# G007X.net
KiCad netlist of a schematic drawn in EAGLE
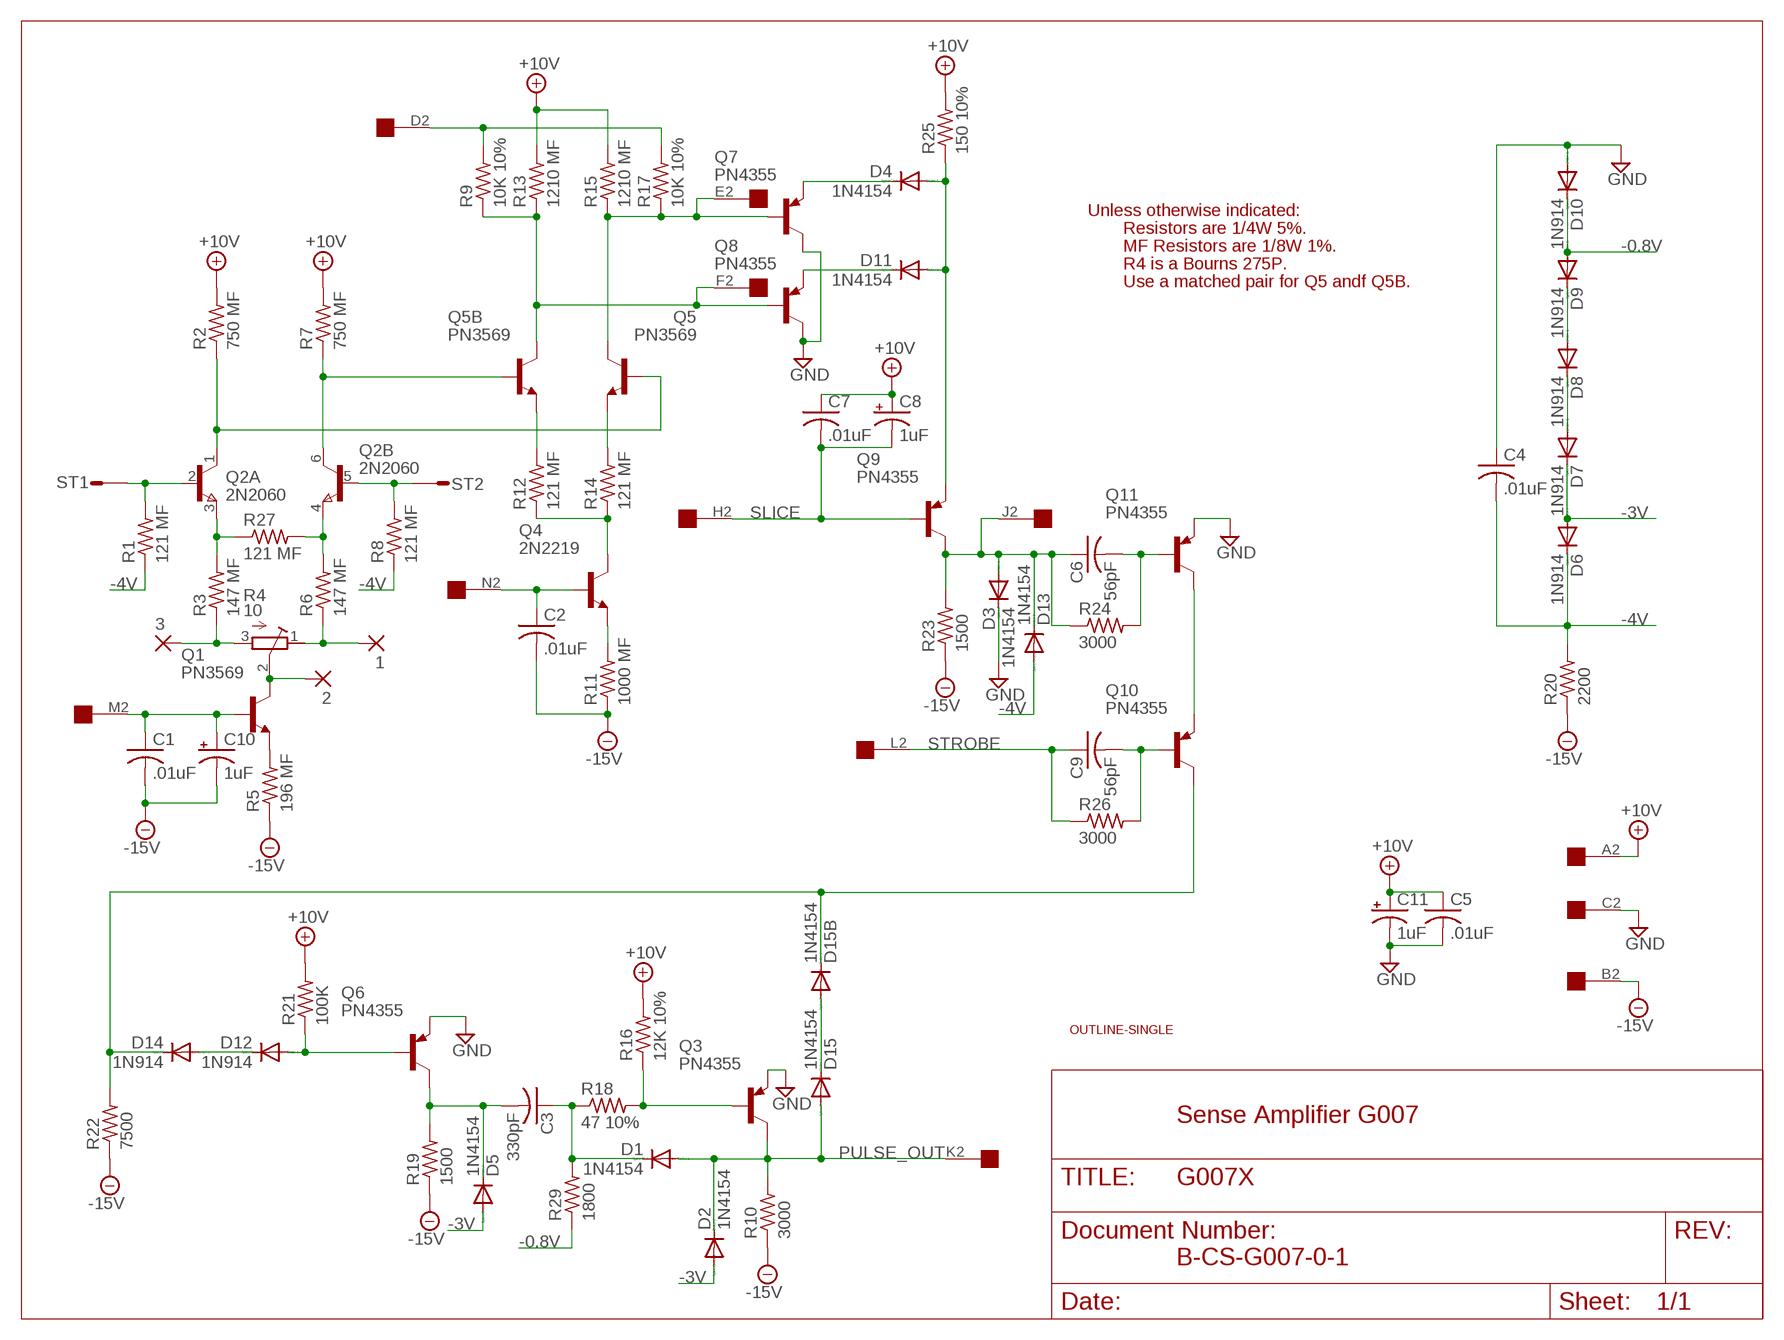
[diagram p0: schematic, sheet 1]

(export (version "E")
  (design (tool "Eeschema 10.0.6"))
  (components
    (comp (ref "1")
      (value "2,54/0,8")
      (footprint "eagle-import:2,54_0,8")
      (libsource (lib "eagle-import") (part "2,54/0,8"))
    )
    (comp (ref "2")
      (value "2,54/0,8")
      (footprint "eagle-import:2,54_0,8")
      (libsource (lib "eagle-import") (part "2,54/0,8"))
    )
    (comp (ref "3")
      (value "2,54/0,8")
      (footprint "eagle-import:2,54_0,8")
      (libsource (lib "eagle-import") (part "2,54/0,8"))
    )
    (comp (ref "C1")
      (value ".01uF")
      (footprint "eagle-import:C050-025X075")
      (libsource (lib "eagle-import") (part "C-US050-025X075"))
    )
    (comp (ref "C2")
      (value ".01uF")
      (footprint "eagle-import:C050-025X075")
      (libsource (lib "eagle-import") (part "C-US050-025X075"))
    )
    (comp (ref "C3")
      (value "330pF")
      (footprint "eagle-import:C075-032X103")
      (libsource (lib "eagle-import") (part "C-US075-032X103"))
    )
    (comp (ref "C4")
      (value ".01uF")
      (footprint "eagle-import:C050-025X075")
      (libsource (lib "eagle-import") (part "C-US050-025X075"))
    )
    (comp (ref "C5")
      (value ".01uF")
      (footprint "eagle-import:C050-025X075")
      (libsource (lib "eagle-import") (part "C-US050-025X075"))
    )
    (comp (ref "C6")
      (value "56pF")
      (footprint "eagle-import:C075-032X103")
      (libsource (lib "eagle-import") (part "C-US075-032X103"))
    )
    (comp (ref "C7")
      (value ".01uF")
      (footprint "eagle-import:C050-025X075")
      (libsource (lib "eagle-import") (part "C-US050-025X075"))
    )
    (comp (ref "C8")
      (value "1uF")
      (footprint "eagle-import:E12-4")
      (libsource (lib "eagle-import") (part "CPOL-USE12-4AXIAL"))
    )
    (comp (ref "C9")
      (value "56pF")
      (footprint "eagle-import:C075-032X103")
      (libsource (lib "eagle-import") (part "C-US075-032X103"))
    )
    (comp (ref "C10")
      (value "1uF")
      (footprint "eagle-import:E12-4")
      (libsource (lib "eagle-import") (part "CPOL-USE12-4AXIAL"))
    )
    (comp (ref "C11")
      (value "1uF")
      (footprint "eagle-import:E12-4")
      (libsource (lib "eagle-import") (part "CPOL-USE12-4AXIAL"))
    )
    (comp (ref "D1")
      (value "1N4154")
      (footprint "eagle-import:DO35-10")
      (libsource (lib "eagle-import") (part "1N4148DO35-10"))
    )
    (comp (ref "D2")
      (value "1N4154")
      (footprint "eagle-import:DO35-10")
      (libsource (lib "eagle-import") (part "1N4148DO35-10"))
    )
    (comp (ref "D3")
      (value "1N4154")
      (footprint "eagle-import:DO35-10")
      (libsource (lib "eagle-import") (part "1N4148DO35-10"))
    )
    (comp (ref "D4")
      (value "1N4154")
      (footprint "eagle-import:DO35-10")
      (libsource (lib "eagle-import") (part "1N4148DO35-10"))
    )
    (comp (ref "D5")
      (value "1N4154")
      (footprint "eagle-import:DO35-10")
      (libsource (lib "eagle-import") (part "1N4148DO35-10"))
    )
    (comp (ref "D6")
      (value "1N914")
      (footprint "eagle-import:DO35-10")
      (libsource (lib "eagle-import") (part "1N4148DO35-10"))
    )
    (comp (ref "D7")
      (value "1N914")
      (footprint "eagle-import:DO35-10")
      (libsource (lib "eagle-import") (part "1N4148DO35-10"))
    )
    (comp (ref "D8")
      (value "1N914")
      (footprint "eagle-import:DO35-10")
      (libsource (lib "eagle-import") (part "1N4148DO35-10"))
    )
    (comp (ref "D9")
      (value "1N914")
      (footprint "eagle-import:DO35-10")
      (libsource (lib "eagle-import") (part "1N4148DO35-10"))
    )
    (comp (ref "D10")
      (value "1N914")
      (footprint "eagle-import:DO35-10")
      (libsource (lib "eagle-import") (part "1N4148DO35-10"))
    )
    (comp (ref "D11")
      (value "1N4154")
      (footprint "eagle-import:DO35-10")
      (libsource (lib "eagle-import") (part "1N4148DO35-10"))
    )
    (comp (ref "D12")
      (value "1N914")
      (footprint "eagle-import:DO35-10")
      (libsource (lib "eagle-import") (part "1N4148DO35-10"))
    )
    (comp (ref "D13")
      (value "1N4154")
      (footprint "eagle-import:DO35-10")
      (libsource (lib "eagle-import") (part "1N4148DO35-10"))
    )
    (comp (ref "D14")
      (value "1N914")
      (footprint "eagle-import:DO35-10")
      (libsource (lib "eagle-import") (part "1N4148DO35-10"))
    )
    (comp (ref "D15")
      (value "1N4154")
      (footprint "eagle-import:DO35-10")
      (libsource (lib "eagle-import") (part "1N4148DO35-10"))
    )
    (comp (ref "D15B")
      (value "1N4154")
      (footprint "eagle-import:DO35-10")
      (libsource (lib "eagle-import") (part "1N4148DO35-10"))
    )
    (comp (ref "Q1")
      (value "PN3569")
      (footprint "eagle-import:TO5")
      (libsource (lib "eagle-import") (part "2N2102"))
    )
    (comp (ref "Q2")
      (value "2N2060")
      (footprint "eagle-import:TO78")
      (libsource (lib "eagle-import") (part "MAT-02H"))
    )
    (comp (ref "Q3")
      (value "PN4355")
      (footprint "eagle-import:TO39")
      (libsource (lib "eagle-import") (part "2N2904"))
    )
    (comp (ref "Q4")
      (value "2N2219")
      (footprint "eagle-import:TO5")
      (libsource (lib "eagle-import") (part "2N2102"))
    )
    (comp (ref "Q5")
      (value "PN3569")
      (footprint "eagle-import:TO5")
      (libsource (lib "eagle-import") (part "2N2102"))
    )
    (comp (ref "Q5B")
      (value "PN3569")
      (footprint "eagle-import:TO5")
      (libsource (lib "eagle-import") (part "2N2102"))
    )
    (comp (ref "Q6")
      (value "PN4355")
      (footprint "eagle-import:TO39")
      (libsource (lib "eagle-import") (part "2N2904"))
    )
    (comp (ref "Q7")
      (value "PN4355")
      (footprint "eagle-import:TO39")
      (libsource (lib "eagle-import") (part "2N2904"))
    )
    (comp (ref "Q8")
      (value "PN4355")
      (footprint "eagle-import:TO39")
      (libsource (lib "eagle-import") (part "2N2904"))
    )
    (comp (ref "Q9")
      (value "PN4355")
      (footprint "eagle-import:TO39")
      (libsource (lib "eagle-import") (part "2N2904"))
    )
    (comp (ref "Q10")
      (value "PN4355")
      (footprint "eagle-import:TO39")
      (libsource (lib "eagle-import") (part "2N2904"))
    )
    (comp (ref "Q11")
      (value "PN4355")
      (footprint "eagle-import:TO39")
      (libsource (lib "eagle-import") (part "2N2904"))
    )
    (comp (ref "R1")
      (value "121 MF")
      (footprint "eagle-import:0207_12")
      (libsource (lib "eagle-import") (part "R-US_0207/12"))
    )
    (comp (ref "R2")
      (value "750 MF")
      (footprint "eagle-import:0207_12")
      (libsource (lib "eagle-import") (part "R-US_0207/12"))
    )
    (comp (ref "R3")
      (value "147 MF")
      (footprint "eagle-import:0207_12")
      (libsource (lib "eagle-import") (part "R-US_0207/12"))
    )
    (comp (ref "R4")
      (value "10")
      (footprint "eagle-import:3006Y")
      (libsource (lib "eagle-import") (part "275P"))
    )
    (comp (ref "R5")
      (value "196 MF")
      (footprint "eagle-import:0207_12")
      (libsource (lib "eagle-import") (part "R-US_0207/12"))
    )
    (comp (ref "R6")
      (value "147 MF")
      (footprint "eagle-import:0207_12")
      (libsource (lib "eagle-import") (part "R-US_0207/12"))
    )
    (comp (ref "R7")
      (value "750 MF")
      (footprint "eagle-import:0207_12")
      (libsource (lib "eagle-import") (part "R-US_0207/12"))
    )
    (comp (ref "R8")
      (value "121 MF")
      (footprint "eagle-import:0207_12")
      (libsource (lib "eagle-import") (part "R-US_0207/12"))
    )
    (comp (ref "R9")
      (value "10K 10%")
      (footprint "eagle-import:0207_10")
      (libsource (lib "eagle-import") (part "R-US_0207/10"))
    )
    (comp (ref "R10")
      (value "3000")
      (footprint "eagle-import:0207_10")
      (libsource (lib "eagle-import") (part "R-US_0207/10"))
    )
    (comp (ref "R11")
      (value "1000 MF")
      (footprint "eagle-import:0207_12")
      (libsource (lib "eagle-import") (part "R-US_0207/12"))
    )
    (comp (ref "R12")
      (value "121 MF")
      (footprint "eagle-import:0207_12")
      (libsource (lib "eagle-import") (part "R-US_0207/12"))
    )
    (comp (ref "R13")
      (value "1210 MF")
      (footprint "eagle-import:0207_12")
      (libsource (lib "eagle-import") (part "R-US_0207/12"))
    )
    (comp (ref "R14")
      (value "121 MF")
      (footprint "eagle-import:0207_12")
      (libsource (lib "eagle-import") (part "R-US_0207/12"))
    )
    (comp (ref "R15")
      (value "1210 MF")
      (footprint "eagle-import:0207_12")
      (libsource (lib "eagle-import") (part "R-US_0207/12"))
    )
    (comp (ref "R16")
      (value "12K 10%")
      (footprint "eagle-import:0207_10")
      (libsource (lib "eagle-import") (part "R-US_0207/10"))
    )
    (comp (ref "R17")
      (value "10K 10%")
      (footprint "eagle-import:0207_10")
      (libsource (lib "eagle-import") (part "R-US_0207/10"))
    )
    (comp (ref "R18")
      (value "47 10%")
      (footprint "eagle-import:0207_10")
      (libsource (lib "eagle-import") (part "R-US_0207/10"))
    )
    (comp (ref "R19")
      (value "1500")
      (footprint "eagle-import:0207_10")
      (libsource (lib "eagle-import") (part "R-US_0207/10"))
    )
    (comp (ref "R20")
      (value "2200")
      (footprint "eagle-import:0207_10")
      (libsource (lib "eagle-import") (part "R-US_0207/10"))
    )
    (comp (ref "R21")
      (value "100K")
      (footprint "eagle-import:0207_10")
      (libsource (lib "eagle-import") (part "R-US_0207/10"))
    )
    (comp (ref "R22")
      (value "7500")
      (footprint "eagle-import:0207_10")
      (libsource (lib "eagle-import") (part "R-US_0207/10"))
    )
    (comp (ref "R23")
      (value "1500")
      (footprint "eagle-import:0207_10")
      (libsource (lib "eagle-import") (part "R-US_0207/10"))
    )
    (comp (ref "R24")
      (value "3000")
      (footprint "eagle-import:0207_10")
      (libsource (lib "eagle-import") (part "R-US_0207/10"))
    )
    (comp (ref "R25")
      (value "150 10%")
      (footprint "eagle-import:0207_10")
      (libsource (lib "eagle-import") (part "R-US_0207/10"))
    )
    (comp (ref "R26")
      (value "3000")
      (footprint "eagle-import:0207_10")
      (libsource (lib "eagle-import") (part "R-US_0207/10"))
    )
    (comp (ref "R27")
      (value "121 MF")
      (footprint "eagle-import:0207_12")
      (libsource (lib "eagle-import") (part "R-US_0207/12"))
    )
    (comp (ref "R29")
      (value "1800")
      (footprint "eagle-import:0207_10")
      (libsource (lib "eagle-import") (part "R-US_0207/10"))
    )
    (comp (ref "ST1")
      (value "ST2,8")
      (footprint "eagle-import:ST2,8")
      (libsource (lib "eagle-import") (part "ST2,8"))
    )
    (comp (ref "ST2")
      (value "ST2,8")
      (footprint "eagle-import:ST2,8")
      (libsource (lib "eagle-import") (part "ST2,8"))
    )
    (comp (ref "U$1")
      (value "OUTLINE-SINGLE")
      (footprint "eagle-import:SINGLE")
      (libsource (lib "eagle-import") (part "OUTLINE-SINGLE"))
    )
    (comp (ref "U$2")
      (value "EDGE-1")
      (footprint "eagle-import:EDGE-CON1")
      (libsource (lib "eagle-import") (part "EDGE-1"))
    )
  )
  (nets
    (net (code "1") (name "+10V") (class "Default")
      (node (ref "C11") (pin "+") (pinfunction "+_+") (pintype "passive"))
      (node (ref "C5") (pin "1") (pinfunction "1_1") (pintype "passive"))
      (node (ref "C7") (pin "1") (pinfunction "1_1") (pintype "passive"))
      (node (ref "C8") (pin "+") (pinfunction "+_+") (pintype "passive"))
      (node (ref "R13") (pin "2") (pinfunction "2_2") (pintype "passive"))
      (node (ref "R15") (pin "2") (pinfunction "2_2") (pintype "passive"))
      (node (ref "R16") (pin "2") (pinfunction "2_2") (pintype "passive"))
      (node (ref "R2") (pin "2") (pinfunction "2_2") (pintype "passive"))
      (node (ref "R21") (pin "2") (pinfunction "2_2") (pintype "passive"))
      (node (ref "R25") (pin "2") (pinfunction "2_2") (pintype "passive"))
      (node (ref "R7") (pin "2") (pinfunction "2_2") (pintype "passive"))
      (node (ref "U$2") (pin "A2") (pinfunction "1_A2") (pintype "bidirectional"))
    )
    (net (code "2") (name "-15V") (class "Default")
      (node (ref "C1") (pin "2") (pinfunction "2_2") (pintype "passive"))
      (node (ref "C10") (pin "-") (pinfunction "-_-") (pintype "passive"))
      (node (ref "C2") (pin "2") (pinfunction "2_2") (pintype "passive"))
      (node (ref "R10") (pin "1") (pinfunction "1_1") (pintype "passive"))
      (node (ref "R11") (pin "1") (pinfunction "1_1") (pintype "passive"))
      (node (ref "R19") (pin "1") (pinfunction "1_1") (pintype "passive"))
      (node (ref "R20") (pin "1") (pinfunction "1_1") (pintype "passive"))
      (node (ref "R22") (pin "1") (pinfunction "1_1") (pintype "passive"))
      (node (ref "R23") (pin "1") (pinfunction "1_1") (pintype "passive"))
      (node (ref "R5") (pin "1") (pinfunction "1_1") (pintype "passive"))
      (node (ref "U$2") (pin "B2") (pinfunction "1_B2") (pintype "bidirectional"))
    )
    (net (code "3") (name "/-0.8V") (class "Default")
      (node (ref "D10") (pin "C") (pinfunction "C_C") (pintype "passive"))
      (node (ref "D9") (pin "A") (pinfunction "A_A") (pintype "passive"))
      (node (ref "R29") (pin "1") (pinfunction "1_1") (pintype "passive"))
    )
    (net (code "4") (name "/-3V") (class "Default")
      (node (ref "D2") (pin "A") (pinfunction "A_A") (pintype "passive"))
      (node (ref "D5") (pin "A") (pinfunction "A_A") (pintype "passive"))
      (node (ref "D6") (pin "A") (pinfunction "A_A") (pintype "passive"))
      (node (ref "D7") (pin "C") (pinfunction "C_C") (pintype "passive"))
    )
    (net (code "5") (name "/-4V") (class "Default")
      (node (ref "C4") (pin "2") (pinfunction "2_2") (pintype "passive"))
      (node (ref "D13") (pin "A") (pinfunction "A_A") (pintype "passive"))
      (node (ref "D6") (pin "C") (pinfunction "C_C") (pintype "passive"))
      (node (ref "R1") (pin "1") (pinfunction "1_1") (pintype "passive"))
      (node (ref "R20") (pin "2") (pinfunction "2_2") (pintype "passive"))
      (node (ref "R8") (pin "1") (pinfunction "1_1") (pintype "passive"))
    )
    (net (code "6") (name "/PULSE_OUT") (class "Default")
      (node (ref "D1") (pin "A") (pinfunction "A_A") (pintype "passive"))
      (node (ref "D15") (pin "A") (pinfunction "A_A") (pintype "passive"))
      (node (ref "D2") (pin "C") (pinfunction "C_C") (pintype "passive"))
      (node (ref "Q3") (pin "3") (pinfunction "C_3") (pintype "passive"))
      (node (ref "R10") (pin "2") (pinfunction "2_2") (pintype "passive"))
      (node (ref "U$2") (pin "K2") (pinfunction "1_K2") (pintype "bidirectional"))
    )
    (net (code "7") (name "/SLICE") (class "Default")
      (node (ref "C7") (pin "2") (pinfunction "2_2") (pintype "passive"))
      (node (ref "C8") (pin "-") (pinfunction "-_-") (pintype "passive"))
      (node (ref "Q9") (pin "2") (pinfunction "B_2") (pintype "passive"))
      (node (ref "U$2") (pin "H2") (pinfunction "1_H2") (pintype "bidirectional"))
    )
    (net (code "8") (name "/STROBE") (class "Default")
      (node (ref "C9") (pin "1") (pinfunction "1_1") (pintype "passive"))
      (node (ref "R26") (pin "1") (pinfunction "1_1") (pintype "passive"))
      (node (ref "U$2") (pin "L2") (pinfunction "1_L2") (pintype "bidirectional"))
    )
    (net (code "9") (name "GND") (class "Default")
      (node (ref "C11") (pin "-") (pinfunction "-_-") (pintype "passive"))
      (node (ref "C4") (pin "1") (pinfunction "1_1") (pintype "passive"))
      (node (ref "C5") (pin "2") (pinfunction "2_2") (pintype "passive"))
      (node (ref "D10") (pin "A") (pinfunction "A_A") (pintype "passive"))
      (node (ref "D3") (pin "C") (pinfunction "C_C") (pintype "passive"))
      (node (ref "Q11") (pin "1") (pinfunction "E_1") (pintype "passive"))
      (node (ref "Q3") (pin "1") (pinfunction "E_1") (pintype "passive"))
      (node (ref "Q6") (pin "1") (pinfunction "E_1") (pintype "passive"))
      (node (ref "Q7") (pin "3") (pinfunction "C_3") (pintype "passive"))
      (node (ref "Q8") (pin "3") (pinfunction "C_3") (pintype "passive"))
      (node (ref "U$2") (pin "C2") (pinfunction "1_C2") (pintype "bidirectional"))
    )
    (net (code "10") (name "Net-(1-P)") (class "Default")
      (node (ref "1") (pin "1") (pinfunction "P_1") (pintype "passive"))
      (node (ref "R4") (pin "1") (pinfunction "A_1") (pintype "passive"))
      (node (ref "R6") (pin "1") (pinfunction "1_1") (pintype "passive"))
    )
    (net (code "11") (name "Net-(2-P)") (class "Default")
      (node (ref "2") (pin "1") (pinfunction "P_1") (pintype "passive"))
      (node (ref "Q1") (pin "3") (pinfunction "C_3") (pintype "passive"))
      (node (ref "R4") (pin "2") (pinfunction "S_2") (pintype "passive"))
    )
    (net (code "12") (name "Net-(3-P)") (class "Default")
      (node (ref "3") (pin "1") (pinfunction "P_1") (pintype "passive"))
      (node (ref "R3") (pin "1") (pinfunction "1_1") (pintype "passive"))
      (node (ref "R4") (pin "3") (pinfunction "E_3") (pintype "passive"))
    )
    (net (code "13") (name "Net-(C3-Pad1)") (class "Default")
      (node (ref "C3") (pin "1") (pinfunction "1_1") (pintype "passive"))
      (node (ref "D1") (pin "C") (pinfunction "C_C") (pintype "passive"))
      (node (ref "R18") (pin "1") (pinfunction "1_1") (pintype "passive"))
      (node (ref "R29") (pin "2") (pinfunction "2_2") (pintype "passive"))
    )
    (net (code "14") (name "Net-(D7-PadA)") (class "Default")
      (node (ref "D7") (pin "A") (pinfunction "A_A") (pintype "passive"))
      (node (ref "D8") (pin "C") (pinfunction "C_C") (pintype "passive"))
    )
    (net (code "15") (name "Net-(D8-PadA)") (class "Default")
      (node (ref "D8") (pin "A") (pinfunction "A_A") (pintype "passive"))
      (node (ref "D9") (pin "C") (pinfunction "C_C") (pintype "passive"))
    )
    (net (code "16") (name "Net-(D12-PadC)") (class "Default")
      (node (ref "D12") (pin "C") (pinfunction "C_C") (pintype "passive"))
      (node (ref "D14") (pin "A") (pinfunction "A_A") (pintype "passive"))
    )
    (net (code "17") (name "Net-(D15-PadC)") (class "Default")
      (node (ref "D15") (pin "C") (pinfunction "C_C") (pintype "passive"))
      (node (ref "D15B") (pin "A") (pinfunction "A_A") (pintype "passive"))
    )
    (net (code "18") (name "Net-(Q1-B)") (class "Default")
      (node (ref "C1") (pin "1") (pinfunction "1_1") (pintype "passive"))
      (node (ref "C10") (pin "+") (pinfunction "+_+") (pintype "passive"))
      (node (ref "Q1") (pin "2") (pinfunction "B_2") (pintype "passive"))
      (node (ref "U$2") (pin "M2") (pinfunction "1_M2") (pintype "bidirectional"))
    )
    (net (code "19") (name "Net-(Q1-E)") (class "Default")
      (node (ref "Q1") (pin "1") (pinfunction "E_1") (pintype "passive"))
      (node (ref "R5") (pin "2") (pinfunction "2_2") (pintype "passive"))
    )
    (net (code "20") (name "Net-(Q2A-B)") (class "Default")
      (node (ref "Q2") (pin "2") (pinfunction "B_2") (pintype "passive"))
      (node (ref "R1") (pin "2") (pinfunction "2_2") (pintype "passive"))
      (node (ref "ST1") (pin "1") (pinfunction "ST_1") (pintype "passive"))
    )
    (net (code "21") (name "Net-(Q2A-C)") (class "Default")
      (node (ref "Q2") (pin "1") (pinfunction "C_1") (pintype "passive"))
      (node (ref "Q5") (pin "2") (pinfunction "B_2") (pintype "passive"))
      (node (ref "R2") (pin "1") (pinfunction "1_1") (pintype "passive"))
    )
    (net (code "22") (name "Net-(Q2A-E)") (class "Default")
      (node (ref "Q2") (pin "3") (pinfunction "E_3") (pintype "passive"))
      (node (ref "R27") (pin "1") (pinfunction "1_1") (pintype "passive"))
      (node (ref "R3") (pin "2") (pinfunction "2_2") (pintype "passive"))
    )
    (net (code "23") (name "Net-(Q2B-B)") (class "Default")
      (node (ref "Q2") (pin "5") (pinfunction "B_5") (pintype "passive"))
      (node (ref "R8") (pin "2") (pinfunction "2_2") (pintype "passive"))
      (node (ref "ST2") (pin "1") (pinfunction "ST_1") (pintype "passive"))
    )
    (net (code "24") (name "Net-(Q2B-C)") (class "Default")
      (node (ref "Q2") (pin "6") (pinfunction "C_6") (pintype "passive"))
      (node (ref "Q5B") (pin "2") (pinfunction "B_2") (pintype "passive"))
      (node (ref "R7") (pin "1") (pinfunction "1_1") (pintype "passive"))
    )
    (net (code "25") (name "Net-(Q2B-E)") (class "Default")
      (node (ref "Q2") (pin "4") (pinfunction "E_4") (pintype "passive"))
      (node (ref "R27") (pin "2") (pinfunction "2_2") (pintype "passive"))
      (node (ref "R6") (pin "2") (pinfunction "2_2") (pintype "passive"))
    )
    (net (code "26") (name "Net-(Q3-B)") (class "Default")
      (node (ref "Q3") (pin "2") (pinfunction "B_2") (pintype "passive"))
      (node (ref "R16") (pin "1") (pinfunction "1_1") (pintype "passive"))
      (node (ref "R18") (pin "2") (pinfunction "2_2") (pintype "passive"))
    )
    (net (code "27") (name "Net-(Q4-B)") (class "Default")
      (node (ref "C2") (pin "1") (pinfunction "1_1") (pintype "passive"))
      (node (ref "Q4") (pin "2") (pinfunction "B_2") (pintype "passive"))
      (node (ref "U$2") (pin "N2") (pinfunction "1_N2") (pintype "bidirectional"))
    )
    (net (code "28") (name "Net-(Q4-C)") (class "Default")
      (node (ref "Q4") (pin "3") (pinfunction "C_3") (pintype "passive"))
      (node (ref "R12") (pin "1") (pinfunction "1_1") (pintype "passive"))
      (node (ref "R14") (pin "1") (pinfunction "1_1") (pintype "passive"))
    )
    (net (code "29") (name "Net-(Q4-E)") (class "Default")
      (node (ref "Q4") (pin "1") (pinfunction "E_1") (pintype "passive"))
      (node (ref "R11") (pin "2") (pinfunction "2_2") (pintype "passive"))
    )
    (net (code "30") (name "Net-(Q5-C)") (class "Default")
      (node (ref "Q5") (pin "3") (pinfunction "C_3") (pintype "passive"))
      (node (ref "Q7") (pin "2") (pinfunction "B_2") (pintype "passive"))
      (node (ref "R15") (pin "1") (pinfunction "1_1") (pintype "passive"))
      (node (ref "R17") (pin "1") (pinfunction "1_1") (pintype "passive"))
      (node (ref "U$2") (pin "E2") (pinfunction "1_E2") (pintype "bidirectional"))
    )
    (net (code "31") (name "Net-(Q5-E)") (class "Default")
      (node (ref "Q5") (pin "1") (pinfunction "E_1") (pintype "passive"))
      (node (ref "R14") (pin "2") (pinfunction "2_2") (pintype "passive"))
    )
    (net (code "32") (name "Net-(Q5B-C)") (class "Default")
      (node (ref "Q5B") (pin "3") (pinfunction "C_3") (pintype "passive"))
      (node (ref "Q8") (pin "2") (pinfunction "B_2") (pintype "passive"))
      (node (ref "R13") (pin "1") (pinfunction "1_1") (pintype "passive"))
      (node (ref "R9") (pin "1") (pinfunction "1_1") (pintype "passive"))
      (node (ref "U$2") (pin "F2") (pinfunction "1_F2") (pintype "bidirectional"))
    )
    (net (code "33") (name "Net-(Q5B-E)") (class "Default")
      (node (ref "Q5B") (pin "1") (pinfunction "E_1") (pintype "passive"))
      (node (ref "R12") (pin "2") (pinfunction "2_2") (pintype "passive"))
    )
    (net (code "34") (name "Net-(Q6-B)") (class "Default")
      (node (ref "D12") (pin "A") (pinfunction "A_A") (pintype "passive"))
      (node (ref "Q6") (pin "2") (pinfunction "B_2") (pintype "passive"))
      (node (ref "R21") (pin "1") (pinfunction "1_1") (pintype "passive"))
    )
    (net (code "35") (name "Net-(Q6-C)") (class "Default")
      (node (ref "C3") (pin "2") (pinfunction "2_2") (pintype "passive"))
      (node (ref "D5") (pin "C") (pinfunction "C_C") (pintype "passive"))
      (node (ref "Q6") (pin "3") (pinfunction "C_3") (pintype "passive"))
      (node (ref "R19") (pin "2") (pinfunction "2_2") (pintype "passive"))
    )
    (net (code "36") (name "Net-(Q7-E)") (class "Default")
      (node (ref "D4") (pin "C") (pinfunction "C_C") (pintype "passive"))
      (node (ref "Q7") (pin "1") (pinfunction "E_1") (pintype "passive"))
    )
    (net (code "37") (name "Net-(Q8-E)") (class "Default")
      (node (ref "D11") (pin "C") (pinfunction "C_C") (pintype "passive"))
      (node (ref "Q8") (pin "1") (pinfunction "E_1") (pintype "passive"))
    )
    (net (code "38") (name "Net-(Q9-C)") (class "Default")
      (node (ref "C6") (pin "1") (pinfunction "1_1") (pintype "passive"))
      (node (ref "D13") (pin "C") (pinfunction "C_C") (pintype "passive"))
      (node (ref "D3") (pin "A") (pinfunction "A_A") (pintype "passive"))
      (node (ref "Q9") (pin "3") (pinfunction "C_3") (pintype "passive"))
      (node (ref "R23") (pin "2") (pinfunction "2_2") (pintype "passive"))
      (node (ref "R24") (pin "1") (pinfunction "1_1") (pintype "passive"))
      (node (ref "U$2") (pin "J2") (pinfunction "1_J2") (pintype "bidirectional"))
    )
    (net (code "39") (name "Net-(Q9-E)") (class "Default")
      (node (ref "D11") (pin "A") (pinfunction "A_A") (pintype "passive"))
      (node (ref "D4") (pin "A") (pinfunction "A_A") (pintype "passive"))
      (node (ref "Q9") (pin "1") (pinfunction "E_1") (pintype "passive"))
      (node (ref "R25") (pin "1") (pinfunction "1_1") (pintype "passive"))
    )
    (net (code "40") (name "Net-(Q10-B)") (class "Default")
      (node (ref "C9") (pin "2") (pinfunction "2_2") (pintype "passive"))
      (node (ref "Q10") (pin "2") (pinfunction "B_2") (pintype "passive"))
      (node (ref "R26") (pin "2") (pinfunction "2_2") (pintype "passive"))
    )
    (net (code "41") (name "Net-(Q10-C)") (class "Default")
      (node (ref "D14") (pin "C") (pinfunction "C_C") (pintype "passive"))
      (node (ref "D15B") (pin "C") (pinfunction "C_C") (pintype "passive"))
      (node (ref "Q10") (pin "3") (pinfunction "C_3") (pintype "passive"))
      (node (ref "R22") (pin "2") (pinfunction "2_2") (pintype "passive"))
    )
    (net (code "42") (name "Net-(Q10-E)") (class "Default")
      (node (ref "Q10") (pin "1") (pinfunction "E_1") (pintype "passive"))
      (node (ref "Q11") (pin "3") (pinfunction "C_3") (pintype "passive"))
    )
    (net (code "43") (name "Net-(Q11-B)") (class "Default")
      (node (ref "C6") (pin "2") (pinfunction "2_2") (pintype "passive"))
      (node (ref "Q11") (pin "2") (pinfunction "B_2") (pintype "passive"))
      (node (ref "R24") (pin "2") (pinfunction "2_2") (pintype "passive"))
    )
    (net (code "44") (name "Net-(U$2D-1)") (class "Default")
      (node (ref "R17") (pin "2") (pinfunction "2_2") (pintype "passive"))
      (node (ref "R9") (pin "2") (pinfunction "2_2") (pintype "passive"))
      (node (ref "U$2") (pin "D2") (pinfunction "1_D2") (pintype "bidirectional"))
    )
  )
)
